# proto1.net
KiCad netlist of a schematic drawn in EAGLE
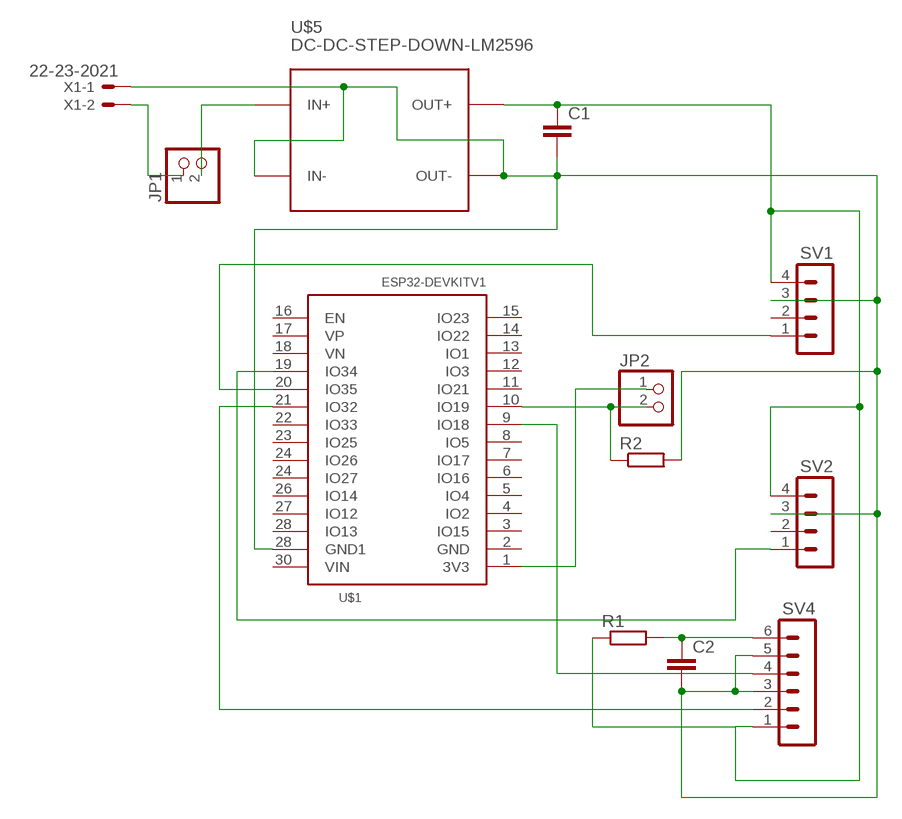
[diagram p0: schematic, sheet 1]

(export (version "E")
  (design (tool "Eeschema 10.0.6"))
  (components
    (comp (ref "C1")
      (value "C2,5-3")
      (footprint "eagle-import:C2.5-3")
      (libsource (lib "eagle-import") (part "C2,5-3"))
    )
    (comp (ref "C2")
      (value "C2,5-3")
      (footprint "eagle-import:C2.5-3")
      (libsource (lib "eagle-import") (part "C2,5-3"))
    )
    (comp (ref "JP1")
      (value "PINHD-1X2/90")
      (footprint "eagle-import:1X02_90")
      (libsource (lib "eagle-import") (part "PINHD-1X2/90"))
    )
    (comp (ref "JP2")
      (value "PINHD-1X2/90")
      (footprint "eagle-import:1X02_90")
      (libsource (lib "eagle-import") (part "PINHD-1X2/90"))
    )
    (comp (ref "R1")
      (value "R-EU_0207/10")
      (footprint "eagle-import:0207_10")
      (libsource (lib "eagle-import") (part "R-EU_0207/10"))
    )
    (comp (ref "R2")
      (value "R-EU_0207/10")
      (footprint "eagle-import:0207_10")
      (libsource (lib "eagle-import") (part "R-EU_0207/10"))
    )
    (comp (ref "SV1")
      (value "MA04-1")
      (footprint "eagle-import:MA04-1")
      (libsource (lib "eagle-import") (part "MA04-1"))
    )
    (comp (ref "SV2")
      (value "MA04-1")
      (footprint "eagle-import:MA04-1")
      (libsource (lib "eagle-import") (part "MA04-1"))
    )
    (comp (ref "SV4")
      (value "MA06-1")
      (footprint "eagle-import:MA06-1")
      (libsource (lib "eagle-import") (part "MA06-1"))
    )
    (comp (ref "U$1")
      (value "ESP32DEVKITV1")
      (footprint "eagle-import:ESP32-DEVKITV1")
      (libsource (lib "eagle-import") (part "ESP32DEVKITV1"))
    )
    (comp (ref "U$5")
      (value "DC-DC-STEP-DOWN-LM2596")
      (footprint "eagle-import:DC-DC-STEP-DOWN-LM2596")
      (libsource (lib "eagle-import") (part "DC-DC-STEP-DOWN-LM2596"))
    )
    (comp (ref "X1")
      (value "22-23-2021")
      (footprint "eagle-import:22-23-2021")
      (fields (field (name "MF") "MOLEX"))
      (libsource (lib "eagle-import") (part "22-23-2021"))
    )
  )
  (nets
    (net (code "1") (name "Net-(C1-Pad1)") (class "Default")
      (node (ref "C1") (pin "1") (pinfunction "1_1") (pintype "passive"))
      (node (ref "R1") (pin "1") (pinfunction "1_1") (pintype "passive"))
      (node (ref "SV1") (pin "4") (pinfunction "4_4") (pintype "passive"))
      (node (ref "SV2") (pin "4") (pinfunction "4_4") (pintype "passive"))
      (node (ref "SV4") (pin "1") (pinfunction "1_1") (pintype "passive"))
      (node (ref "U$5") (pin "OUT+") (pinfunction "OUT+_OUT+") (pintype "bidirectional"))
    )
    (net (code "2") (name "Net-(C2-Pad1)") (class "Default")
      (node (ref "C2") (pin "1") (pinfunction "1_1") (pintype "passive"))
      (node (ref "R1") (pin "2") (pinfunction "2_2") (pintype "passive"))
      (node (ref "SV4") (pin "6") (pinfunction "6_6") (pintype "passive"))
    )
    (net (code "3") (name "Net-(JP1-Pad2)") (class "Default")
      (node (ref "JP1") (pin "2") (pinfunction "2_2") (pintype "passive"))
      (node (ref "U$5") (pin "IN+") (pinfunction "IN+_IN+") (pintype "bidirectional"))
    )
    (net (code "4") (name "Net-(U$1-3V3)") (class "Default")
      (node (ref "JP2") (pin "1") (pinfunction "1_1") (pintype "passive"))
      (node (ref "U$1") (pin "1") (pinfunction "3V3_1") (pintype "bidirectional"))
    )
    (net (code "5") (name "Net-(U$1-GND1)") (class "Default")
      (node (ref "C1") (pin "2") (pinfunction "2_2") (pintype "passive"))
      (node (ref "C2") (pin "2") (pinfunction "2_2") (pintype "passive"))
      (node (ref "R2") (pin "2") (pinfunction "2_2") (pintype "passive"))
      (node (ref "SV1") (pin "3") (pinfunction "3_3") (pintype "passive"))
      (node (ref "SV2") (pin "3") (pinfunction "3_3") (pintype "passive"))
      (node (ref "SV4") (pin "3") (pinfunction "3_3") (pintype "passive"))
      (node (ref "SV4") (pin "5") (pinfunction "5_5") (pintype "passive"))
      (node (ref "U$1") (pin "28") (pinfunction "GND1_28") (pintype "bidirectional"))
      (node (ref "U$5") (pin "IN-") (pinfunction "IN-_IN-") (pintype "bidirectional"))
      (node (ref "U$5") (pin "OUT-") (pinfunction "OUT-_OUT-") (pintype "bidirectional"))
      (node (ref "X1") (pin "1") (pinfunction "S_1") (pintype "passive"))
    )
    (net (code "6") (name "Net-(U$1-IO18)") (class "Default")
      (node (ref "SV4") (pin "4") (pinfunction "4_4") (pintype "passive"))
      (node (ref "U$1") (pin "9") (pinfunction "IO18_9") (pintype "bidirectional"))
    )
    (net (code "7") (name "Net-(U$1-IO19)") (class "Default")
      (node (ref "JP2") (pin "2") (pinfunction "2_2") (pintype "passive"))
      (node (ref "R2") (pin "1") (pinfunction "1_1") (pintype "passive"))
      (node (ref "U$1") (pin "10") (pinfunction "IO19_10") (pintype "bidirectional"))
    )
    (net (code "8") (name "Net-(U$1-IO32)") (class "Default")
      (node (ref "SV4") (pin "2") (pinfunction "2_2") (pintype "passive"))
      (node (ref "U$1") (pin "21") (pinfunction "IO32_21") (pintype "bidirectional"))
    )
    (net (code "9") (name "Net-(U$1-IO34)") (class "Default")
      (node (ref "SV2") (pin "1") (pinfunction "1_1") (pintype "passive"))
      (node (ref "U$1") (pin "19") (pinfunction "IO34_19") (pintype "bidirectional"))
    )
    (net (code "10") (name "Net-(U$1-IO35)") (class "Default")
      (node (ref "SV1") (pin "1") (pinfunction "1_1") (pintype "passive"))
      (node (ref "U$1") (pin "20") (pinfunction "IO35_20") (pintype "bidirectional"))
    )
    (net (code "11") (name "Net-(X1B-S)") (class "Default")
      (node (ref "JP1") (pin "1") (pinfunction "1_1") (pintype "passive"))
      (node (ref "X1") (pin "2") (pinfunction "S_2") (pintype "passive"))
    )
    (net (code "12") (name "unconnected-(SV1-Pad2)") (class "Default")
      (node (ref "SV1") (pin "2") (pinfunction "2_2") (pintype "passive"))
    )
    (net (code "13") (name "unconnected-(SV2-Pad2)") (class "Default")
      (node (ref "SV2") (pin "2") (pinfunction "2_2") (pintype "passive"))
    )
    (net (code "14") (name "unconnected-(U$1-EN-Pad16)") (class "Default")
      (node (ref "U$1") (pin "16") (pinfunction "EN_16") (pintype "bidirectional"))
    )
    (net (code "15") (name "unconnected-(U$1-GND-Pad2)") (class "Default")
      (node (ref "U$1") (pin "2") (pinfunction "GND_2") (pintype "bidirectional"))
    )
    (net (code "16") (name "unconnected-(U$1-IO1-Pad13)") (class "Default")
      (node (ref "U$1") (pin "13") (pinfunction "IO1_13") (pintype "bidirectional"))
    )
    (net (code "17") (name "unconnected-(U$1-IO2-Pad4)") (class "Default")
      (node (ref "U$1") (pin "4") (pinfunction "IO2_4") (pintype "bidirectional"))
    )
    (net (code "18") (name "unconnected-(U$1-IO3-Pad12)") (class "Default")
      (node (ref "U$1") (pin "12") (pinfunction "IO3_12") (pintype "bidirectional"))
    )
    (net (code "19") (name "unconnected-(U$1-IO4-Pad5)") (class "Default")
      (node (ref "U$1") (pin "5") (pinfunction "IO4_5") (pintype "bidirectional"))
    )
    (net (code "20") (name "unconnected-(U$1-IO5-Pad8)") (class "Default")
      (node (ref "U$1") (pin "8") (pinfunction "IO5_8") (pintype "bidirectional"))
    )
    (net (code "21") (name "unconnected-(U$1-IO12-Pad27)") (class "Default")
      (node (ref "U$1") (pin "27") (pinfunction "IO12_27") (pintype "bidirectional"))
    )
    (net (code "22") (name "unconnected-(U$1-IO13-Pad28)") (class "Default")
      (node (ref "U$1") (pin "28") (pinfunction "IO13_28") (pintype "bidirectional"))
    )
    (net (code "23") (name "unconnected-(U$1-IO14-Pad26)") (class "Default")
      (node (ref "U$1") (pin "26") (pinfunction "IO14_26") (pintype "bidirectional"))
    )
    (net (code "24") (name "unconnected-(U$1-IO15-Pad3)") (class "Default")
      (node (ref "U$1") (pin "3") (pinfunction "IO15_3") (pintype "bidirectional"))
    )
    (net (code "25") (name "unconnected-(U$1-IO16-Pad6)") (class "Default")
      (node (ref "U$1") (pin "6") (pinfunction "IO16_6") (pintype "bidirectional"))
    )
    (net (code "26") (name "unconnected-(U$1-IO17-Pad7)") (class "Default")
      (node (ref "U$1") (pin "7") (pinfunction "IO17_7") (pintype "bidirectional"))
    )
    (net (code "27") (name "unconnected-(U$1-IO21-Pad11)") (class "Default")
      (node (ref "U$1") (pin "11") (pinfunction "IO21_11") (pintype "bidirectional"))
    )
    (net (code "28") (name "unconnected-(U$1-IO22-Pad14)") (class "Default")
      (node (ref "U$1") (pin "14") (pinfunction "IO22_14") (pintype "bidirectional"))
    )
    (net (code "29") (name "unconnected-(U$1-IO23-Pad15)") (class "Default")
      (node (ref "U$1") (pin "15") (pinfunction "IO23_15") (pintype "bidirectional"))
    )
    (net (code "30") (name "unconnected-(U$1-IO25-Pad23)") (class "Default")
      (node (ref "U$1") (pin "23") (pinfunction "IO25_23") (pintype "bidirectional"))
    )
    (net (code "31") (name "unconnected-(U$1-IO26-Pad24)") (class "Default")
      (node (ref "U$1") (pin "24") (pinfunction "IO26_24") (pintype "bidirectional"))
    )
    (net (code "32") (name "unconnected-(U$1-IO27-Pad24)") (class "Default")
      (node (ref "U$1") (pin "24") (pinfunction "IO27_24") (pintype "bidirectional"))
    )
    (net (code "33") (name "unconnected-(U$1-IO33-Pad22)") (class "Default")
      (node (ref "U$1") (pin "22") (pinfunction "IO33_22") (pintype "bidirectional"))
    )
    (net (code "34") (name "unconnected-(U$1-VIN-Pad30)") (class "Default")
      (node (ref "U$1") (pin "30") (pinfunction "VIN_30") (pintype "bidirectional"))
    )
    (net (code "35") (name "unconnected-(U$1-VN-Pad18)") (class "Default")
      (node (ref "U$1") (pin "18") (pinfunction "VN_18") (pintype "bidirectional"))
    )
    (net (code "36") (name "unconnected-(U$1-VP-Pad17)") (class "Default")
      (node (ref "U$1") (pin "17") (pinfunction "VP_17") (pintype "bidirectional"))
    )
  )
)
